# rev2.net
KiCad netlist of a schematic drawn in EAGLE
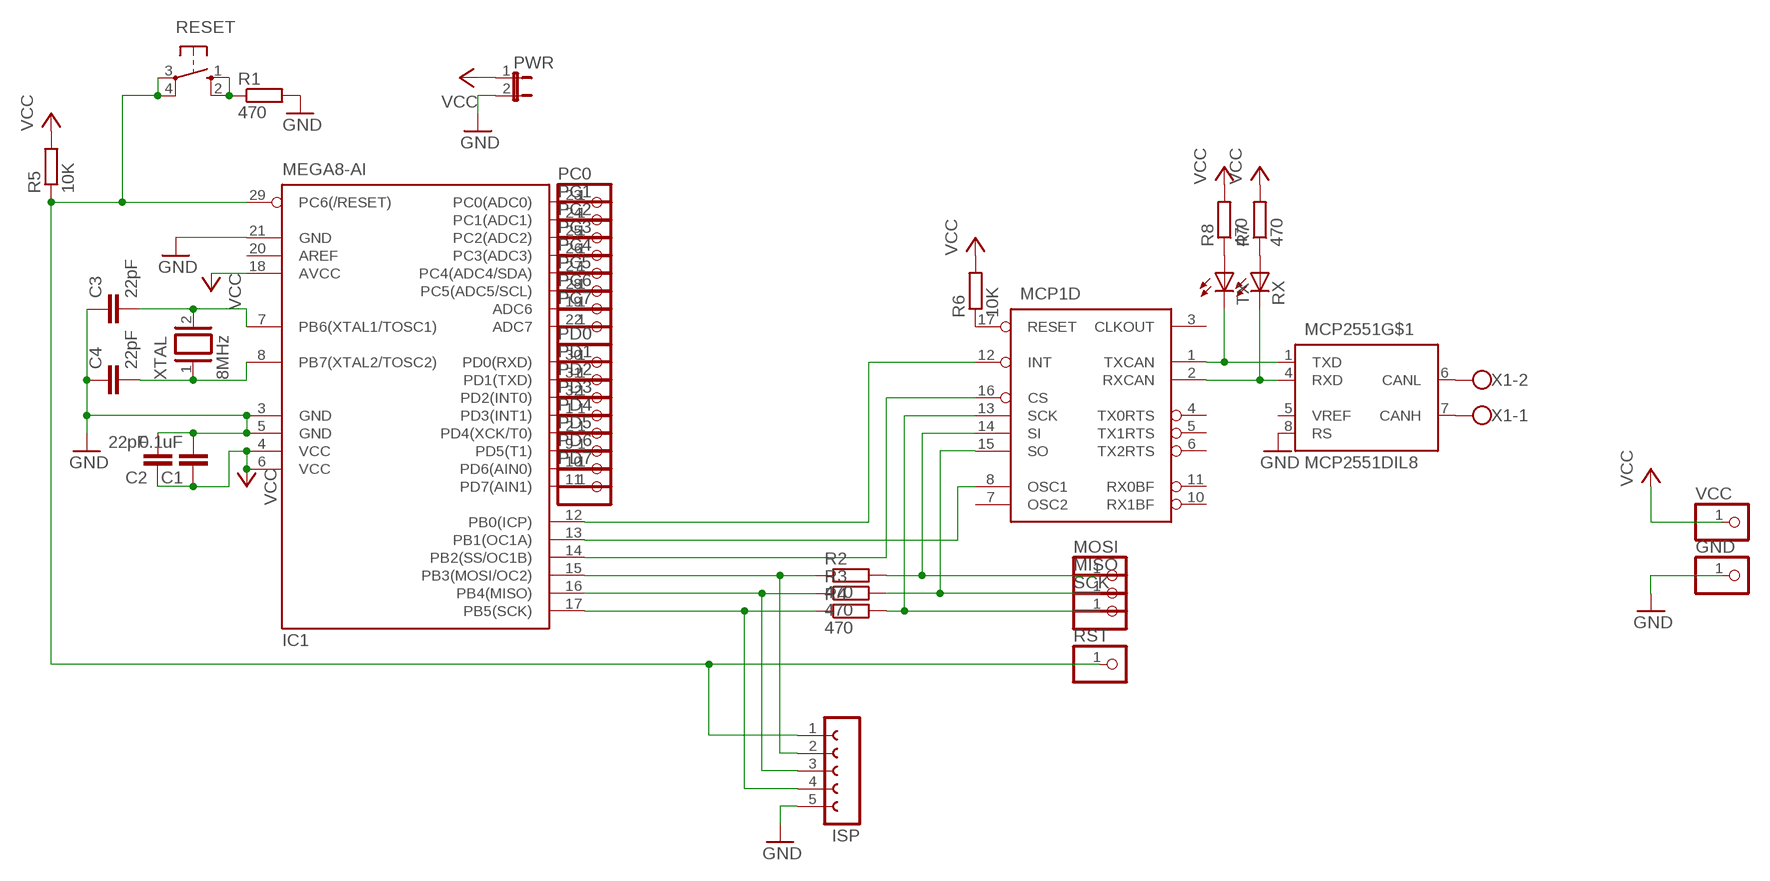
[diagram p0: schematic, sheet 1]

(export (version "E")
  (design (tool "Eeschema 10.0.6"))
  (components
    (comp (ref "C1")
      (value "0.1uF")
      (footprint "eagle-import:C0603")
      (libsource (lib "eagle-import") (part "C-EUC0603"))
    )
    (comp (ref "C2")
      (value "22pF")
      (footprint "eagle-import:C0603")
      (libsource (lib "eagle-import") (part "C-EUC0603"))
    )
    (comp (ref "C3")
      (value "22pF")
      (footprint "eagle-import:C0603")
      (libsource (lib "eagle-import") (part "C-EUC0603"))
    )
    (comp (ref "C4")
      (value "22pF")
      (footprint "eagle-import:C0603")
      (libsource (lib "eagle-import") (part "C-EUC0603"))
    )
    (comp (ref "GND")
      (value "PINHD-1X1")
      (footprint "eagle-import:1X01")
      (libsource (lib "eagle-import") (part "PINHD-1X1"))
    )
    (comp (ref "IC1")
      (value "MEGA8-AI")
      (footprint "eagle-import:TQFP32-08")
      (fields (field (name "MPN") "ATMEGA8-16AU") (field (name "OC_NEWARK") "unknown"))
      (libsource (lib "eagle-import") (part "MEGA8-AI"))
    )
    (comp (ref "ISP")
      (value "FE05-1")
      (footprint "eagle-import:FE05-1")
      (libsource (lib "eagle-import") (part "FE05-1"))
    )
    (comp (ref "MCP1")
      (value "MCP2515P")
      (footprint "eagle-import:DIL18")
      (libsource (lib "eagle-import") (part "MCP2515P"))
    )
    (comp (ref "MCP2551")
      (value "MCP2551DIL8")
      (footprint "eagle-import:DIL08")
      (libsource (lib "eagle-import") (part "MCP2551DIL8"))
    )
    (comp (ref "MISO")
      (value "PINHD-1X1")
      (footprint "eagle-import:1X01")
      (libsource (lib "eagle-import") (part "PINHD-1X1"))
    )
    (comp (ref "MOSI")
      (value "PINHD-1X1")
      (footprint "eagle-import:1X01")
      (libsource (lib "eagle-import") (part "PINHD-1X1"))
    )
    (comp (ref "PC0")
      (value "PINHD-1X1")
      (footprint "eagle-import:1X01")
      (libsource (lib "eagle-import") (part "PINHD-1X1"))
    )
    (comp (ref "PC1")
      (value "PINHD-1X1")
      (footprint "eagle-import:1X01")
      (libsource (lib "eagle-import") (part "PINHD-1X1"))
    )
    (comp (ref "PC2")
      (value "PINHD-1X1")
      (footprint "eagle-import:1X01")
      (libsource (lib "eagle-import") (part "PINHD-1X1"))
    )
    (comp (ref "PC3")
      (value "PINHD-1X1")
      (footprint "eagle-import:1X01")
      (libsource (lib "eagle-import") (part "PINHD-1X1"))
    )
    (comp (ref "PC4")
      (value "PINHD-1X1")
      (footprint "eagle-import:1X01")
      (libsource (lib "eagle-import") (part "PINHD-1X1"))
    )
    (comp (ref "PC5")
      (value "PINHD-1X1")
      (footprint "eagle-import:1X01")
      (libsource (lib "eagle-import") (part "PINHD-1X1"))
    )
    (comp (ref "PC6")
      (value "PINHD-1X1")
      (footprint "eagle-import:1X01")
      (libsource (lib "eagle-import") (part "PINHD-1X1"))
    )
    (comp (ref "PC7")
      (value "PINHD-1X1")
      (footprint "eagle-import:1X01")
      (libsource (lib "eagle-import") (part "PINHD-1X1"))
    )
    (comp (ref "PD0")
      (value "PINHD-1X1")
      (footprint "eagle-import:1X01")
      (libsource (lib "eagle-import") (part "PINHD-1X1"))
    )
    (comp (ref "PD1")
      (value "PINHD-1X1")
      (footprint "eagle-import:1X01")
      (libsource (lib "eagle-import") (part "PINHD-1X1"))
    )
    (comp (ref "PD2")
      (value "PINHD-1X1")
      (footprint "eagle-import:1X01")
      (libsource (lib "eagle-import") (part "PINHD-1X1"))
    )
    (comp (ref "PD3")
      (value "PINHD-1X1")
      (footprint "eagle-import:1X01")
      (libsource (lib "eagle-import") (part "PINHD-1X1"))
    )
    (comp (ref "PD4")
      (value "PINHD-1X1")
      (footprint "eagle-import:1X01")
      (libsource (lib "eagle-import") (part "PINHD-1X1"))
    )
    (comp (ref "PD5")
      (value "PINHD-1X1")
      (footprint "eagle-import:1X01")
      (libsource (lib "eagle-import") (part "PINHD-1X1"))
    )
    (comp (ref "PD6")
      (value "PINHD-1X1")
      (footprint "eagle-import:1X01")
      (libsource (lib "eagle-import") (part "PINHD-1X1"))
    )
    (comp (ref "PD7")
      (value "PINHD-1X1")
      (footprint "eagle-import:1X01")
      (libsource (lib "eagle-import") (part "PINHD-1X1"))
    )
    (comp (ref "PWR")
      (value "JUMPER-2PTH")
      (footprint "eagle-import:1X02")
      (libsource (lib "eagle-import") (part "JUMPER-2PTH"))
    )
    (comp (ref "R1")
      (value "470")
      (footprint "eagle-import:R0603")
      (libsource (lib "eagle-import") (part "R-EU_R0603"))
    )
    (comp (ref "R2")
      (value "470")
      (footprint "eagle-import:R0603")
      (libsource (lib "eagle-import") (part "R-EU_R0603"))
    )
    (comp (ref "R3")
      (value "470")
      (footprint "eagle-import:R0603")
      (libsource (lib "eagle-import") (part "R-EU_R0603"))
    )
    (comp (ref "R4")
      (value "470")
      (footprint "eagle-import:R0603")
      (libsource (lib "eagle-import") (part "R-EU_R0603"))
    )
    (comp (ref "R5")
      (value "10K")
      (footprint "eagle-import:R0603")
      (libsource (lib "eagle-import") (part "R-EU_R0603"))
    )
    (comp (ref "R6")
      (value "10K")
      (footprint "eagle-import:R0603")
      (libsource (lib "eagle-import") (part "R-EU_R0603"))
    )
    (comp (ref "R7")
      (value "470")
      (footprint "eagle-import:R0603")
      (libsource (lib "eagle-import") (part "R-EU_R0603"))
    )
    (comp (ref "R8")
      (value "470")
      (footprint "eagle-import:R0603")
      (libsource (lib "eagle-import") (part "R-EU_R0603"))
    )
    (comp (ref "RESET")
      (value "10-XX")
      (footprint "eagle-import:B3F-10XX")
      (fields (field (name "MPN") "B3F-1000"))
      (libsource (lib "eagle-import") (part "10-XX"))
    )
    (comp (ref "RST")
      (value "PINHD-1X1")
      (footprint "eagle-import:1X01")
      (libsource (lib "eagle-import") (part "PINHD-1X1"))
    )
    (comp (ref "RX")
      (value "LEDCHIP-LED0603")
      (footprint "eagle-import:CHIP-LED0603")
      (libsource (lib "eagle-import") (part "LEDCHIP-LED0603"))
    )
    (comp (ref "SCK")
      (value "PINHD-1X1")
      (footprint "eagle-import:1X01")
      (libsource (lib "eagle-import") (part "PINHD-1X1"))
    )
    (comp (ref "TX")
      (value "LEDCHIP-LED0603")
      (footprint "eagle-import:CHIP-LED0603")
      (libsource (lib "eagle-import") (part "LEDCHIP-LED0603"))
    )
    (comp (ref "VCC")
      (value "PINHD-1X1")
      (footprint "eagle-import:1X01")
      (libsource (lib "eagle-import") (part "PINHD-1X1"))
    )
    (comp (ref "X1")
      (value "W237-102")
      (footprint "eagle-import:W237-102")
      (fields (field (name "MPN") "237-102"))
      (libsource (lib "eagle-import") (part "W237-102"))
    )
    (comp (ref "XTAL")
      (value "8MHz")
      (footprint "eagle-import:QS")
      (libsource (lib "eagle-import") (part "XTAL/S"))
    )
  )
  (nets
    (net (code "1") (name "GND") (class "Default")
      (node (ref "C1") (pin "2") (pinfunction "2_2") (pintype "passive"))
      (node (ref "C2") (pin "2") (pinfunction "2_2") (pintype "passive"))
      (node (ref "C3") (pin "1") (pinfunction "1_1") (pintype "passive"))
      (node (ref "C4") (pin "1") (pinfunction "1_1") (pintype "passive"))
      (node (ref "GND") (pin "1") (pinfunction "1_1") (pintype "passive"))
      (node (ref "IC1") (pin "21") (pinfunction "GND_21") (pintype "power_in"))
      (node (ref "IC1") (pin "3") (pinfunction "GND_3") (pintype "power_in"))
      (node (ref "IC1") (pin "5") (pinfunction "GND_5") (pintype "power_in"))
      (node (ref "ISP") (pin "5") (pinfunction "5_5") (pintype "passive"))
      (node (ref "MCP2551") (pin "8") (pinfunction "RS_8") (pintype "bidirectional"))
      (node (ref "PWR") (pin "2") (pinfunction "2_2") (pintype "passive"))
      (node (ref "R1") (pin "2") (pinfunction "2_2") (pintype "passive"))
    )
    (net (code "2") (name "Net-(IC1-ADC6)") (class "Default")
      (node (ref "IC1") (pin "19") (pinfunction "ADC6_19") (pintype "bidirectional"))
      (node (ref "PC6") (pin "1") (pinfunction "1_1") (pintype "passive"))
    )
    (net (code "3") (name "Net-(IC1-ADC7)") (class "Default")
      (node (ref "IC1") (pin "22") (pinfunction "ADC7_22") (pintype "bidirectional"))
      (node (ref "PC7") (pin "1") (pinfunction "1_1") (pintype "passive"))
    )
    (net (code "4") (name "Net-(IC1-PB0(ICP))") (class "Default")
      (node (ref "IC1") (pin "12") (pinfunction "PB0(ICP)_12") (pintype "bidirectional"))
      (node (ref "MCP1") (pin "12") (pinfunction "INT_12") (pintype "output"))
    )
    (net (code "5") (name "Net-(IC1-PB1(OC1A))") (class "Default")
      (node (ref "IC1") (pin "13") (pinfunction "PB1(OC1A)_13") (pintype "bidirectional"))
      (node (ref "MCP1") (pin "8") (pinfunction "OSC1_8") (pintype "input"))
    )
    (net (code "6") (name "Net-(IC1-PB2(SS{slash}OC1B))") (class "Default")
      (node (ref "IC1") (pin "14") (pinfunction "PB2(SS/OC1B)_14") (pintype "bidirectional"))
      (node (ref "MCP1") (pin "16") (pinfunction "CS_16") (pintype "input"))
    )
    (net (code "7") (name "Net-(IC1-PB3(MOSI{slash}OC2))") (class "Default")
      (node (ref "IC1") (pin "15") (pinfunction "PB3(MOSI/OC2)_15") (pintype "bidirectional"))
      (node (ref "ISP") (pin "2") (pinfunction "2_2") (pintype "passive"))
      (node (ref "R2") (pin "1") (pinfunction "1_1") (pintype "passive"))
    )
    (net (code "8") (name "Net-(IC1-PB4(MISO))") (class "Default")
      (node (ref "IC1") (pin "16") (pinfunction "PB4(MISO)_16") (pintype "bidirectional"))
      (node (ref "ISP") (pin "3") (pinfunction "3_3") (pintype "passive"))
      (node (ref "R3") (pin "1") (pinfunction "1_1") (pintype "passive"))
    )
    (net (code "9") (name "Net-(IC1-PB5(SCK))") (class "Default")
      (node (ref "IC1") (pin "17") (pinfunction "PB5(SCK)_17") (pintype "bidirectional"))
      (node (ref "ISP") (pin "4") (pinfunction "4_4") (pintype "passive"))
      (node (ref "R4") (pin "1") (pinfunction "1_1") (pintype "passive"))
    )
    (net (code "10") (name "Net-(IC1-PB6(XTAL1{slash}TOSC1))") (class "Default")
      (node (ref "C3") (pin "2") (pinfunction "2_2") (pintype "passive"))
      (node (ref "IC1") (pin "7") (pinfunction "PB6(XTAL1/TOSC1)_7") (pintype "bidirectional"))
      (node (ref "XTAL") (pin "2") (pinfunction "2_2") (pintype "passive"))
    )
    (net (code "11") (name "Net-(IC1-PB7(XTAL2{slash}TOSC2))") (class "Default")
      (node (ref "C4") (pin "2") (pinfunction "2_2") (pintype "passive"))
      (node (ref "IC1") (pin "8") (pinfunction "PB7(XTAL2/TOSC2)_8") (pintype "bidirectional"))
      (node (ref "XTAL") (pin "1") (pinfunction "1_1") (pintype "passive"))
    )
    (net (code "12") (name "Net-(IC1-PC0(ADC0))") (class "Default")
      (node (ref "IC1") (pin "23") (pinfunction "PC0(ADC0)_23") (pintype "bidirectional"))
      (node (ref "PC0") (pin "1") (pinfunction "1_1") (pintype "passive"))
    )
    (net (code "13") (name "Net-(IC1-PC1(ADC1))") (class "Default")
      (node (ref "IC1") (pin "24") (pinfunction "PC1(ADC1)_24") (pintype "bidirectional"))
      (node (ref "PC1") (pin "1") (pinfunction "1_1") (pintype "passive"))
    )
    (net (code "14") (name "Net-(IC1-PC2(ADC2))") (class "Default")
      (node (ref "IC1") (pin "25") (pinfunction "PC2(ADC2)_25") (pintype "bidirectional"))
      (node (ref "PC2") (pin "1") (pinfunction "1_1") (pintype "passive"))
    )
    (net (code "15") (name "Net-(IC1-PC3(ADC3))") (class "Default")
      (node (ref "IC1") (pin "26") (pinfunction "PC3(ADC3)_26") (pintype "bidirectional"))
      (node (ref "PC3") (pin "1") (pinfunction "1_1") (pintype "passive"))
    )
    (net (code "16") (name "Net-(IC1-PC4(ADC4{slash}SDA))") (class "Default")
      (node (ref "IC1") (pin "27") (pinfunction "PC4(ADC4/SDA)_27") (pintype "bidirectional"))
      (node (ref "PC4") (pin "1") (pinfunction "1_1") (pintype "passive"))
    )
    (net (code "17") (name "Net-(IC1-PC5(ADC5{slash}SCL))") (class "Default")
      (node (ref "IC1") (pin "28") (pinfunction "PC5(ADC5/SCL)_28") (pintype "bidirectional"))
      (node (ref "PC5") (pin "1") (pinfunction "1_1") (pintype "passive"))
    )
    (net (code "18") (name "Net-(IC1-PC6({slash}RESET))") (class "Default")
      (node (ref "IC1") (pin "29") (pinfunction "PC6(/RESET)_29") (pintype "bidirectional"))
      (node (ref "ISP") (pin "1") (pinfunction "1_1") (pintype "passive"))
      (node (ref "R5") (pin "1") (pinfunction "1_1") (pintype "passive"))
      (node (ref "RESET") (pin "3") (pinfunction "P_3") (pintype "passive"))
      (node (ref "RESET") (pin "4") (pinfunction "P1_4") (pintype "passive"))
      (node (ref "RST") (pin "1") (pinfunction "1_1") (pintype "passive"))
    )
    (net (code "19") (name "Net-(IC1-PD0(RXD))") (class "Default")
      (node (ref "IC1") (pin "30") (pinfunction "PD0(RXD)_30") (pintype "bidirectional"))
      (node (ref "PD0") (pin "1") (pinfunction "1_1") (pintype "passive"))
    )
    (net (code "20") (name "Net-(IC1-PD1(TXD))") (class "Default")
      (node (ref "IC1") (pin "31") (pinfunction "PD1(TXD)_31") (pintype "bidirectional"))
      (node (ref "PD1") (pin "1") (pinfunction "1_1") (pintype "passive"))
    )
    (net (code "21") (name "Net-(IC1-PD2(INT0))") (class "Default")
      (node (ref "IC1") (pin "32") (pinfunction "PD2(INT0)_32") (pintype "bidirectional"))
      (node (ref "PD2") (pin "1") (pinfunction "1_1") (pintype "passive"))
    )
    (net (code "22") (name "Net-(IC1-PD3(INT1))") (class "Default")
      (node (ref "IC1") (pin "1") (pinfunction "PD3(INT1)_1") (pintype "bidirectional"))
      (node (ref "PD3") (pin "1") (pinfunction "1_1") (pintype "passive"))
    )
    (net (code "23") (name "Net-(IC1-PD4(XCK{slash}T0))") (class "Default")
      (node (ref "IC1") (pin "2") (pinfunction "PD4(XCK/T0)_2") (pintype "bidirectional"))
      (node (ref "PD4") (pin "1") (pinfunction "1_1") (pintype "passive"))
    )
    (net (code "24") (name "Net-(IC1-PD5(T1))") (class "Default")
      (node (ref "IC1") (pin "9") (pinfunction "PD5(T1)_9") (pintype "bidirectional"))
      (node (ref "PD5") (pin "1") (pinfunction "1_1") (pintype "passive"))
    )
    (net (code "25") (name "Net-(IC1-PD6(AIN0))") (class "Default")
      (node (ref "IC1") (pin "10") (pinfunction "PD6(AIN0)_10") (pintype "bidirectional"))
      (node (ref "PD6") (pin "1") (pinfunction "1_1") (pintype "passive"))
    )
    (net (code "26") (name "Net-(IC1-PD7(AIN1))") (class "Default")
      (node (ref "IC1") (pin "11") (pinfunction "PD7(AIN1)_11") (pintype "bidirectional"))
      (node (ref "PD7") (pin "1") (pinfunction "1_1") (pintype "passive"))
    )
    (net (code "27") (name "Net-(MCP1A-RESET)") (class "Default")
      (node (ref "MCP1") (pin "17") (pinfunction "RESET_17") (pintype "input"))
      (node (ref "R6") (pin "1") (pinfunction "1_1") (pintype "passive"))
    )
    (net (code "28") (name "Net-(MCP1A-RXCAN)") (class "Default")
      (node (ref "MCP1") (pin "2") (pinfunction "RXCAN_2") (pintype "input"))
      (node (ref "MCP2551") (pin "4") (pinfunction "RXD_4") (pintype "bidirectional"))
      (node (ref "RX") (pin "C") (pinfunction "C_C") (pintype "passive"))
    )
    (net (code "29") (name "Net-(MCP1A-SCK)") (class "Default")
      (node (ref "MCP1") (pin "13") (pinfunction "SCK_13") (pintype "input"))
      (node (ref "R4") (pin "2") (pinfunction "2_2") (pintype "passive"))
      (node (ref "SCK") (pin "1") (pinfunction "1_1") (pintype "passive"))
    )
    (net (code "30") (name "Net-(MCP1A-SI)") (class "Default")
      (node (ref "MCP1") (pin "14") (pinfunction "SI_14") (pintype "input"))
      (node (ref "MOSI") (pin "1") (pinfunction "1_1") (pintype "passive"))
      (node (ref "R2") (pin "2") (pinfunction "2_2") (pintype "passive"))
    )
    (net (code "31") (name "Net-(MCP1A-SO)") (class "Default")
      (node (ref "MCP1") (pin "15") (pinfunction "SO_15") (pintype "output"))
      (node (ref "MISO") (pin "1") (pinfunction "1_1") (pintype "passive"))
      (node (ref "R3") (pin "2") (pinfunction "2_2") (pintype "passive"))
    )
    (net (code "32") (name "Net-(MCP1A-TXCAN)") (class "Default")
      (node (ref "MCP1") (pin "1") (pinfunction "TXCAN_1") (pintype "output"))
      (node (ref "MCP2551") (pin "1") (pinfunction "TXD_1") (pintype "bidirectional"))
      (node (ref "TX") (pin "C") (pinfunction "C_C") (pintype "passive"))
    )
    (net (code "33") (name "Net-(MCP2551A-CANH)") (class "Default")
      (node (ref "MCP2551") (pin "7") (pinfunction "CANH_7") (pintype "bidirectional"))
      (node (ref "X1") (pin "1") (pinfunction "KL_1") (pintype "passive"))
    )
    (net (code "34") (name "Net-(MCP2551A-CANL)") (class "Default")
      (node (ref "MCP2551") (pin "6") (pinfunction "CANL_6") (pintype "bidirectional"))
      (node (ref "X1") (pin "2") (pinfunction "KL_2") (pintype "passive"))
    )
    (net (code "35") (name "Net-(R7-Pad1)") (class "Default")
      (node (ref "R7") (pin "1") (pinfunction "1_1") (pintype "passive"))
      (node (ref "RX") (pin "A") (pinfunction "A_A") (pintype "passive"))
    )
    (net (code "36") (name "Net-(R8-Pad1)") (class "Default")
      (node (ref "R8") (pin "1") (pinfunction "1_1") (pintype "passive"))
      (node (ref "TX") (pin "A") (pinfunction "A_A") (pintype "passive"))
    )
    (net (code "37") (name "Net-(RESET-S)") (class "Default")
      (node (ref "R1") (pin "1") (pinfunction "1_1") (pintype "passive"))
      (node (ref "RESET") (pin "1") (pinfunction "S_1") (pintype "passive"))
      (node (ref "RESET") (pin "2") (pinfunction "S1_2") (pintype "passive"))
    )
    (net (code "38") (name "VCC") (class "Default")
      (node (ref "C1") (pin "1") (pinfunction "1_1") (pintype "passive"))
      (node (ref "C2") (pin "1") (pinfunction "1_1") (pintype "passive"))
      (node (ref "IC1") (pin "18") (pinfunction "AVCC_18") (pintype "power_in"))
      (node (ref "IC1") (pin "4") (pinfunction "VCC_4") (pintype "power_in"))
      (node (ref "IC1") (pin "6") (pinfunction "VCC_6") (pintype "power_in"))
      (node (ref "PWR") (pin "1") (pinfunction "1_1") (pintype "passive"))
      (node (ref "R5") (pin "2") (pinfunction "2_2") (pintype "passive"))
      (node (ref "R6") (pin "2") (pinfunction "2_2") (pintype "passive"))
      (node (ref "R7") (pin "2") (pinfunction "2_2") (pintype "passive"))
      (node (ref "R8") (pin "2") (pinfunction "2_2") (pintype "passive"))
      (node (ref "VCC") (pin "1") (pinfunction "1_1") (pintype "passive"))
    )
    (net (code "39") (name "unconnected-(IC1-AREF-Pad20)") (class "Default")
      (node (ref "IC1") (pin "20") (pinfunction "AREF_20") (pintype "passive"))
    )
    (net (code "40") (name "unconnected-(MCP1A-CLKOUT-Pad3)") (class "Default")
      (node (ref "MCP1") (pin "3") (pinfunction "CLKOUT_3") (pintype "output"))
    )
    (net (code "41") (name "unconnected-(MCP1A-OSC2-Pad7)") (class "Default")
      (node (ref "MCP1") (pin "7") (pinfunction "OSC2_7") (pintype "input"))
    )
    (net (code "42") (name "unconnected-(MCP1A-RX0BF-Pad11)") (class "Default")
      (node (ref "MCP1") (pin "11") (pinfunction "RX0BF_11") (pintype "output"))
    )
    (net (code "43") (name "unconnected-(MCP1A-RX1BF-Pad10)") (class "Default")
      (node (ref "MCP1") (pin "10") (pinfunction "RX1BF_10") (pintype "output"))
    )
    (net (code "44") (name "unconnected-(MCP1A-TX0RTS-Pad4)") (class "Default")
      (node (ref "MCP1") (pin "4") (pinfunction "TX0RTS_4") (pintype "input"))
    )
    (net (code "45") (name "unconnected-(MCP1A-TX1RTS-Pad5)") (class "Default")
      (node (ref "MCP1") (pin "5") (pinfunction "TX1RTS_5") (pintype "input"))
    )
    (net (code "46") (name "unconnected-(MCP1A-TX2RTS-Pad6)") (class "Default")
      (node (ref "MCP1") (pin "6") (pinfunction "TX2RTS_6") (pintype "input"))
    )
    (net (code "47") (name "unconnected-(MCP2551A-VREF-Pad5)") (class "Default")
      (node (ref "MCP2551") (pin "5") (pinfunction "VREF_5") (pintype "bidirectional"))
    )
  )
)
